# PC_CONNECTIONS.net
KiCad netlist of a schematic drawn in Altium Designer
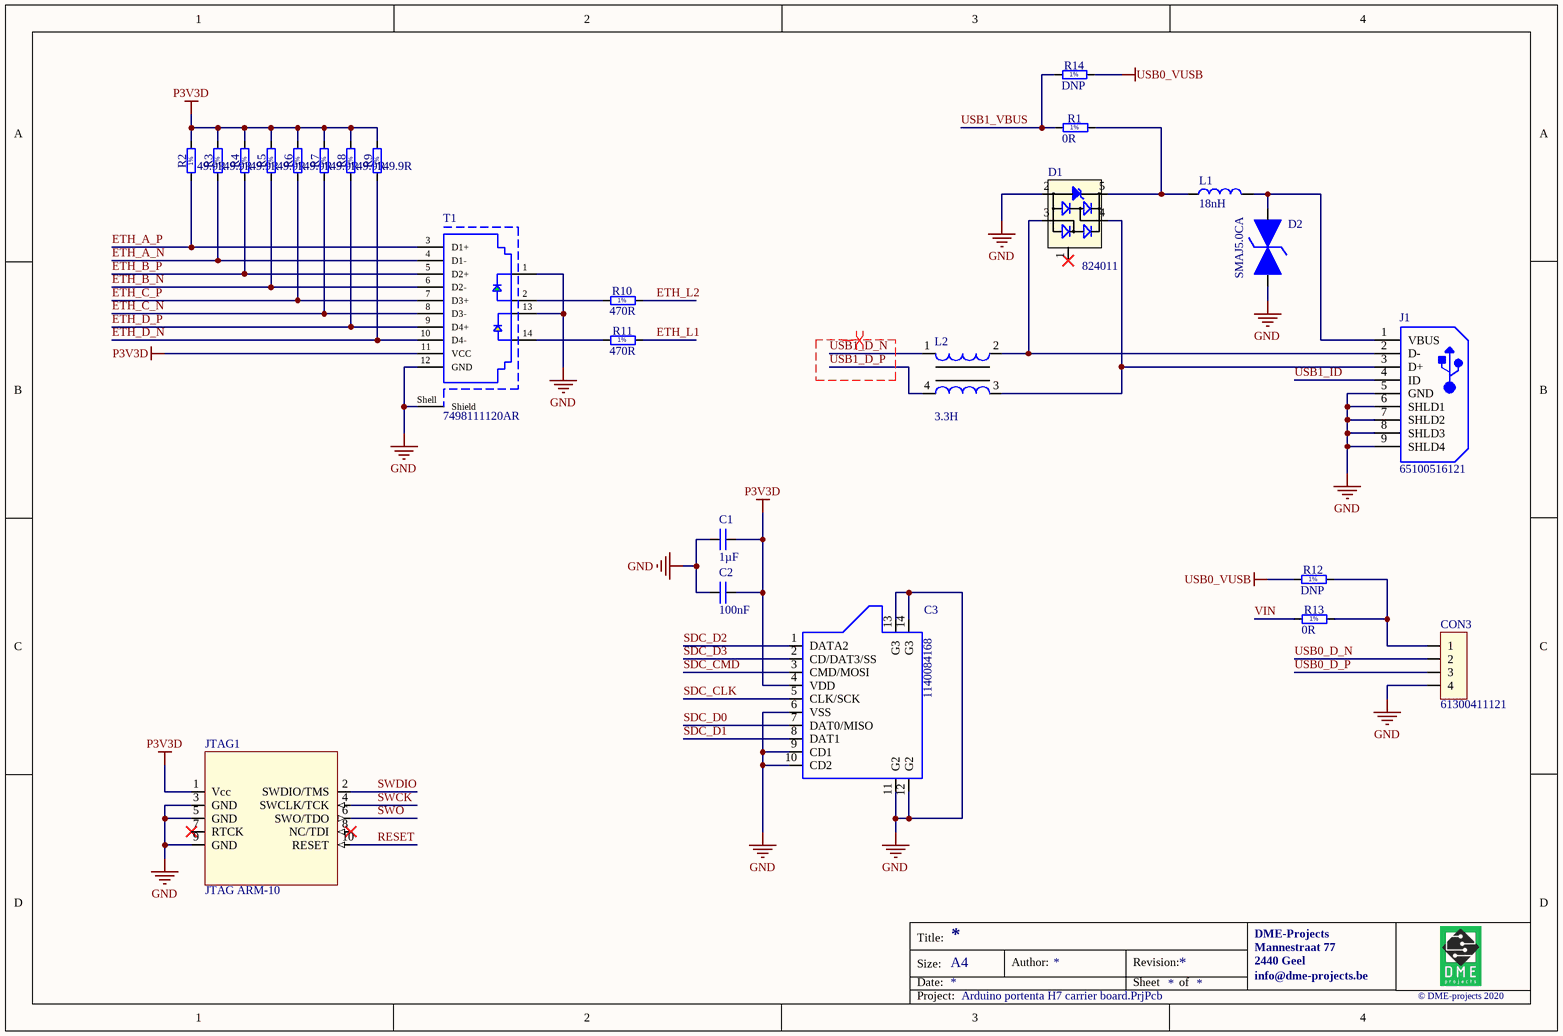
[diagram p0: PC CONNECTIONS.SchDoc]

(export (version "E")
  (design (tool "Eeschema 10.0.6"))
  (components
    (comp (ref "C1")
      (value "1µF")
      (footprint "C0603")
      (description "generic 0603 capacitor")
      (fields (field (name "MFG") "generic") (field (name "TOLERANCE") "0.05"))
      (libsource (lib "MIRION Technologies (CANBERRA Olen) NV") (part "cap"))
    )
    (comp (ref "C2")
      (value "100nF")
      (footprint "C0603")
      (description "generic 0603 capacitor")
      (fields (field (name "TOLERANCE") "0.05") (field (name "MFG") "generic"))
      (libsource (lib "MIRION Technologies (CANBERRA Olen) NV") (part "cap"))
    )
    (comp (ref "C3")
      (value "1140084168")
      (footprint "Amphenol_MicroSD_Connector")
      (description "Micro SD; Conn; IC Socket; ; Right Angle; PCB Mount; MicroSD Ser.")
      (libsource (lib "MIRION Technologies (CANBERRA Olen) NV") (part "1140084168"))
    )
    (comp (ref "CON3")
      (value "61300411121")
      (footprint "61300411121")
      (description "CONN HEADER VERT 4POS 2.54MM")
      (libsource (lib "MIRION Technologies (CANBERRA Olen) NV") (part "CON4"))
    )
    (comp (ref "D1")
      (value "824011")
      (footprint "ATML-5TS1_N")
      (description "Trans Voltage Suppressor Diode, 5V V(RWM), Unidirectional, 1 Element, Silicon")
      (libsource (lib "MIRION Technologies (CANBERRA Olen) NV") (part "WE-TVS-HS-5"))
    )
    (comp (ref "D2")
      (value "SMAJ5.0CA")
      (footprint "FP-SMAJ-MFG")
      (libsource (lib "MIRION Technologies (CANBERRA Olen) NV") (part "be7038aff30a2d1172baa952aa6ae09"))
    )
    (comp (ref "J1")
      (value "65100516121")
      (footprint "WE-65100516121_V")
      (description "CONN RCPT USB2.0 MINI B SMD R/A")
      (libsource (lib "MIRION Technologies (CANBERRA Olen) NV") (part "USB-5-4SHLD"))
    )
    (comp (ref "JTAG1")
      (value "JTAG ARM-10")
      (footprint "62501021621")
      (description "JTAG ARM 10 pin interface connector 2mm pitch")
      (libsource (lib "MIRION Technologies (CANBERRA Olen) NV") (part "10P-JTAG"))
    )
    (comp (ref "L1")
      (value "742792641")
      (footprint "SMD-0603")
      (description "FERRITE BEAD 300 OHM 0603 1LN")
      (fields (field (name "TOLERANCE") "25%") (field (name "INDUCTANCE") "18nH"))
      (libsource (lib "MIRION Technologies (CANBERRA Olen) NV") (part "IND_SINGLE"))
    )
    (comp (ref "L2")
      (value "744232090")
      (footprint "WE-CNSW-1206")
      (description "Data Line Filter, 2 Function(s), 50V, 0.37A")
      (fields (field (name "INDUCTANCE") "3.3H") (field (name "TOLERANCE") "25%"))
      (libsource (lib "MIRION Technologies (CANBERRA Olen) NV") (part "PAS-IND-INDUCTOR-4A"))
    )
    (comp (ref "R1")
      (value "0R")
      (footprint "R0603")
      (description "generic 0603 Thick film resistor")
      (fields (field (name "POWER") "100mW") (field (name "TOLERANCE") "0.01"))
      (libsource (lib "MIRION Technologies (CANBERRA Olen) NV") (part "res_1pct"))
    )
    (comp (ref "R2")
      (value "49.9R")
      (footprint "R0603")
      (description "generic 0603 Thick film resistor")
      (fields (field (name "VOLTAGE") "75V") (field (name "MFG") "generic"))
      (libsource (lib "MIRION Technologies (CANBERRA Olen) NV") (part "res_1pct"))
    )
    (comp (ref "R3")
      (value "49.9R")
      (footprint "R0603")
      (description "generic 0603 Thick film resistor")
      (fields (field (name "VOLTAGE") "75V") (field (name "MFG") "generic"))
      (libsource (lib "MIRION Technologies (CANBERRA Olen) NV") (part "res_1pct"))
    )
    (comp (ref "R4")
      (value "49.9R")
      (footprint "R0603")
      (description "generic 0603 Thick film resistor")
      (fields (field (name "VOLTAGE") "75V") (field (name "MFG") "generic"))
      (libsource (lib "MIRION Technologies (CANBERRA Olen) NV") (part "res_1pct"))
    )
    (comp (ref "R5")
      (value "49.9R")
      (footprint "R0603")
      (description "generic 0603 Thick film resistor")
      (fields (field (name "VOLTAGE") "75V") (field (name "MFG") "generic"))
      (libsource (lib "MIRION Technologies (CANBERRA Olen) NV") (part "res_1pct"))
    )
    (comp (ref "R6")
      (value "49.9R")
      (footprint "R0603")
      (description "generic 0603 Thick film resistor")
      (fields (field (name "VOLTAGE") "75V") (field (name "MFG") "generic"))
      (libsource (lib "MIRION Technologies (CANBERRA Olen) NV") (part "res_1pct"))
    )
    (comp (ref "R7")
      (value "49.9R")
      (footprint "R0603")
      (description "generic 0603 Thick film resistor")
      (fields (field (name "VOLTAGE") "75V") (field (name "MFG") "generic"))
      (libsource (lib "MIRION Technologies (CANBERRA Olen) NV") (part "res_1pct"))
    )
    (comp (ref "R8")
      (value "49.9R")
      (footprint "R0603")
      (description "generic 0603 Thick film resistor")
      (fields (field (name "VOLTAGE") "75V") (field (name "MFG") "generic"))
      (libsource (lib "MIRION Technologies (CANBERRA Olen) NV") (part "res_1pct"))
    )
    (comp (ref "R9")
      (value "49.9R")
      (footprint "R0603")
      (description "generic 0603 Thick film resistor")
      (fields (field (name "VOLTAGE") "75V") (field (name "MFG") "generic"))
      (libsource (lib "MIRION Technologies (CANBERRA Olen) NV") (part "res_1pct"))
    )
    (comp (ref "R10")
      (value "470R")
      (footprint "R0603")
      (description "generic 0603 Thick film resistor")
      (fields (field (name "POWER") "100mW") (field (name "TOLERANCE") "0.01"))
      (libsource (lib "MIRION Technologies (CANBERRA Olen) NV") (part "res_1pct"))
    )
    (comp (ref "R11")
      (value "470R")
      (footprint "R0603")
      (description "generic 0603 Thick film resistor")
      (fields (field (name "POWER") "100mW") (field (name "TOLERANCE") "0.01"))
      (libsource (lib "MIRION Technologies (CANBERRA Olen) NV") (part "res_1pct"))
    )
    (comp (ref "R12")
      (value "DNP")
      (footprint "R0603")
      (description "generic 0603 Thick film resistor")
      (fields (field (name "VOLTAGE") "75V") (field (name "POWER") "100mW"))
      (libsource (lib "MIRION Technologies (CANBERRA Olen) NV") (part "res_1pct"))
    )
    (comp (ref "R13")
      (value "0R")
      (footprint "R0603")
      (description "generic 0603 Thick film resistor")
      (fields (field (name "POWER") "100mW") (field (name "TOLERANCE") "0.01"))
      (libsource (lib "MIRION Technologies (CANBERRA Olen) NV") (part "res_1pct"))
    )
    (comp (ref "R14")
      (value "DNP")
      (footprint "R0603")
      (description "generic 0603 Thick film resistor")
      (fields (field (name "VOLTAGE") "75V") (field (name "POWER") "100mW"))
      (libsource (lib "MIRION Technologies (CANBERRA Olen) NV") (part "res_1pct"))
    )
    (comp (ref "T1")
      (value "7498111120AR")
      (footprint "7498111120AR")
      (description "WE-RJ45 LAN Transformer, SMT, 10/100/1000 Base-T, Port 1x1, Tab Up")
      (fields (field (name "MANUFACTURER") "Wurth Elektronik"))
      (libsource (lib "MIRION Technologies (CANBERRA Olen) NV") (part "7498111120AR"))
    )
  )
  (nets
    (net (code "1") (name "/ETH_A_N") (class "Default")
      (node (ref "R3") (pin "1") (pinfunction "1_1") (pintype "passive"))
      (node (ref "T1") (pin "4") (pinfunction "D1-_4") (pintype "passive"))
    )
    (net (code "2") (name "/ETH_A_P") (class "Default")
      (node (ref "R2") (pin "1") (pinfunction "1_1") (pintype "passive"))
      (node (ref "T1") (pin "3") (pinfunction "D1+_3") (pintype "passive"))
    )
    (net (code "3") (name "/ETH_B_N") (class "Default")
      (node (ref "R5") (pin "1") (pinfunction "1_1") (pintype "passive"))
      (node (ref "T1") (pin "6") (pinfunction "D2-_6") (pintype "passive"))
    )
    (net (code "4") (name "/ETH_B_P") (class "Default")
      (node (ref "R4") (pin "1") (pinfunction "1_1") (pintype "passive"))
      (node (ref "T1") (pin "5") (pinfunction "D2+_5") (pintype "passive"))
    )
    (net (code "5") (name "/ETH_C_N") (class "Default")
      (node (ref "R7") (pin "1") (pinfunction "1_1") (pintype "passive"))
      (node (ref "T1") (pin "8") (pinfunction "D3-_8") (pintype "passive"))
    )
    (net (code "6") (name "/ETH_C_P") (class "Default")
      (node (ref "R6") (pin "1") (pinfunction "1_1") (pintype "passive"))
      (node (ref "T1") (pin "7") (pinfunction "D3+_7") (pintype "passive"))
    )
    (net (code "7") (name "/ETH_D_N") (class "Default")
      (node (ref "R9") (pin "1") (pinfunction "1_1") (pintype "passive"))
      (node (ref "T1") (pin "10") (pinfunction "D4-_10") (pintype "passive"))
    )
    (net (code "8") (name "/ETH_D_P") (class "Default")
      (node (ref "R8") (pin "1") (pinfunction "1_1") (pintype "passive"))
      (node (ref "T1") (pin "9") (pinfunction "D4+_9") (pintype "passive"))
    )
    (net (code "9") (name "/ETH_L1") (class "Default")
      (node (ref "R11") (pin "2") (pinfunction "2_2") (pintype "passive"))
    )
    (net (code "10") (name "/ETH_L2") (class "Default")
      (node (ref "R10") (pin "2") (pinfunction "2_2") (pintype "passive"))
    )
    (net (code "11") (name "/RESET") (class "Default")
      (node (ref "JTAG1") (pin "10") (pinfunction "RESET_10") (pintype "input"))
    )
    (net (code "12") (name "/SDC_CLK") (class "Default")
      (node (ref "C3") (pin "5") (pinfunction "CLK/SCK_5") (pintype "passive"))
    )
    (net (code "13") (name "/SDC_CMD") (class "Default")
      (node (ref "C3") (pin "3") (pinfunction "CMD/MOSI_3") (pintype "passive"))
    )
    (net (code "14") (name "/SDC_D0") (class "Default")
      (node (ref "C3") (pin "7") (pinfunction "DAT0/MISO_7") (pintype "passive"))
    )
    (net (code "15") (name "/SDC_D1") (class "Default")
      (node (ref "C3") (pin "8") (pinfunction "DAT1_8") (pintype "passive"))
    )
    (net (code "16") (name "/SDC_D2") (class "Default")
      (node (ref "C3") (pin "1") (pinfunction "DATA2_1") (pintype "passive"))
    )
    (net (code "17") (name "/SDC_D3") (class "Default")
      (node (ref "C3") (pin "2") (pinfunction "CD/DAT3/SS_2") (pintype "passive"))
    )
    (net (code "18") (name "/SWCK") (class "Default")
      (node (ref "JTAG1") (pin "4") (pinfunction "SWCLK/TCK_4") (pintype "input"))
    )
    (net (code "19") (name "/SWDIO") (class "Default")
      (node (ref "JTAG1") (pin "2") (pinfunction "SWDIO/TMS_2") (pintype "bidirectional"))
    )
    (net (code "20") (name "/SWO") (class "Default")
      (node (ref "JTAG1") (pin "6") (pinfunction "SWO/TDO_6") (pintype "output"))
    )
    (net (code "21") (name "/USB0_D_N") (class "Default")
      (node (ref "CON3") (pin "2") (pinfunction "2_2") (pintype "passive"))
    )
    (net (code "22") (name "/USB0_D_P") (class "Default")
      (node (ref "CON3") (pin "3") (pinfunction "3_3") (pintype "passive"))
    )
    (net (code "23") (name "/USB1_D_N") (class "Default")
      (node (ref "L2") (pin "1") (pinfunction "1_1") (pintype "passive"))
    )
    (net (code "24") (name "/USB1_D_P") (class "Default")
      (node (ref "L2") (pin "4") (pinfunction "4_4") (pintype "passive"))
    )
    (net (code "25") (name "/USB1_ID") (class "Default")
      (node (ref "J1") (pin "4") (pinfunction "ID_4") (pintype "passive"))
    )
    (net (code "26") (name "/USB1_VBUS") (class "Default")
      (node (ref "R1") (pin "1") (pinfunction "1_1") (pintype "passive"))
      (node (ref "R14") (pin "1") (pinfunction "1_1") (pintype "passive"))
    )
    (net (code "27") (name "/VIN") (class "Default")
      (node (ref "R13") (pin "1") (pinfunction "1_1") (pintype "passive"))
    )
    (net (code "28") (name "GND") (class "Default")
      (node (ref "C1") (pin "2") (pinfunction "2_2") (pintype "passive"))
      (node (ref "C2") (pin "1") (pinfunction "1_1") (pintype "passive"))
      (node (ref "C3") (pin "10") (pinfunction "CD2_10") (pintype "passive"))
      (node (ref "C3") (pin "11") (pinfunction "G2_11") (pintype "power_in"))
      (node (ref "C3") (pin "12") (pinfunction "G2_12") (pintype "power_in"))
      (node (ref "C3") (pin "13") (pinfunction "G3_13") (pintype "power_in"))
      (node (ref "C3") (pin "14") (pinfunction "G3_14") (pintype "power_in"))
      (node (ref "C3") (pin "6") (pinfunction "VSS_6") (pintype "power_in"))
      (node (ref "C3") (pin "9") (pinfunction "CD1_9") (pintype "passive"))
      (node (ref "CON3") (pin "4") (pinfunction "4_4") (pintype "passive"))
      (node (ref "D1") (pin "2") (pinfunction "GND_2") (pintype "passive"))
      (node (ref "D2") (pin "1") (pinfunction "1_1") (pintype "passive"))
      (node (ref "J1") (pin "5") (pinfunction "GND_5") (pintype "power_in"))
      (node (ref "J1") (pin "6") (pinfunction "SHLD1_6") (pintype "passive"))
      (node (ref "J1") (pin "7") (pinfunction "SHLD2_7") (pintype "passive"))
      (node (ref "J1") (pin "8") (pinfunction "SHLD3_8") (pintype "passive"))
      (node (ref "J1") (pin "9") (pinfunction "SHLD4_9") (pintype "passive"))
      (node (ref "JTAG1") (pin "3") (pinfunction "GND_3") (pintype "power_in"))
      (node (ref "JTAG1") (pin "5") (pinfunction "GND_5") (pintype "power_in"))
      (node (ref "JTAG1") (pin "9") (pinfunction "GND_9") (pintype "power_in"))
      (node (ref "T1") (pin "1") (pinfunction "1_1") (pintype "passive"))
      (node (ref "T1") (pin "12") (pinfunction "GND_12") (pintype "passive"))
      (node (ref "T1") (pin "13") (pinfunction "13_13") (pintype "passive"))
      (node (ref "T1") (pin "Shell") (pinfunction "Shield_Shell") (pintype "passive"))
    )
    (net (code "29") (name "Net-(CON3-Pad1)") (class "Default")
      (node (ref "CON3") (pin "1") (pinfunction "1_1") (pintype "passive"))
      (node (ref "R12") (pin "2") (pinfunction "2_2") (pintype "passive"))
      (node (ref "R13") (pin "2") (pinfunction "2_2") (pintype "passive"))
    )
    (net (code "30") (name "Net-(D1-I{slash}O1)") (class "Default")
      (node (ref "D1") (pin "3") (pinfunction "I/O1_3") (pintype "passive"))
      (node (ref "J1") (pin "2") (pinfunction "D-_2") (pintype "passive"))
      (node (ref "L2") (pin "2") (pinfunction "2_2") (pintype "passive"))
    )
    (net (code "31") (name "Net-(D1-I{slash}O2)") (class "Default")
      (node (ref "D1") (pin "4") (pinfunction "I/O2_4") (pintype "passive"))
      (node (ref "J1") (pin "3") (pinfunction "D+_3") (pintype "passive"))
      (node (ref "L2") (pin "3") (pinfunction "3_3") (pintype "passive"))
    )
    (net (code "32") (name "Net-(D1-VDD)") (class "Default")
      (node (ref "D1") (pin "5") (pinfunction "VDD_5") (pintype "passive"))
      (node (ref "L1") (pin "1") (pinfunction "1_1") (pintype "passive"))
      (node (ref "R1") (pin "2") (pinfunction "2_2") (pintype "passive"))
    )
    (net (code "33") (name "Net-(J1-VBUS)") (class "Default")
      (node (ref "D2") (pin "2") (pinfunction "2_2") (pintype "passive"))
      (node (ref "J1") (pin "1") (pinfunction "VBUS_1") (pintype "power_in"))
      (node (ref "L1") (pin "2") (pinfunction "2_2") (pintype "passive"))
    )
    (net (code "34") (name "Net-(R10-Pad1)") (class "Default")
      (node (ref "R10") (pin "1") (pinfunction "1_1") (pintype "passive"))
      (node (ref "T1") (pin "2") (pinfunction "2_2") (pintype "passive"))
    )
    (net (code "35") (name "Net-(R11-Pad1)") (class "Default")
      (node (ref "R11") (pin "1") (pinfunction "1_1") (pintype "passive"))
      (node (ref "T1") (pin "14") (pinfunction "14_14") (pintype "passive"))
    )
    (net (code "36") (name "P3V3D") (class "Default")
      (node (ref "C1") (pin "1") (pinfunction "1_1") (pintype "passive"))
      (node (ref "C2") (pin "2") (pinfunction "2_2") (pintype "passive"))
      (node (ref "C3") (pin "4") (pinfunction "VDD_4") (pintype "power_in"))
      (node (ref "JTAG1") (pin "1") (pinfunction "Vcc_1") (pintype "power_in"))
      (node (ref "R2") (pin "2") (pinfunction "2_2") (pintype "passive"))
      (node (ref "R3") (pin "2") (pinfunction "2_2") (pintype "passive"))
      (node (ref "R4") (pin "2") (pinfunction "2_2") (pintype "passive"))
      (node (ref "R5") (pin "2") (pinfunction "2_2") (pintype "passive"))
      (node (ref "R6") (pin "2") (pinfunction "2_2") (pintype "passive"))
      (node (ref "R7") (pin "2") (pinfunction "2_2") (pintype "passive"))
      (node (ref "R8") (pin "2") (pinfunction "2_2") (pintype "passive"))
      (node (ref "R9") (pin "2") (pinfunction "2_2") (pintype "passive"))
      (node (ref "T1") (pin "11") (pinfunction "VCC_11") (pintype "passive"))
    )
    (net (code "37") (name "USB0_VUSB") (class "Default")
      (node (ref "R12") (pin "1") (pinfunction "1_1") (pintype "passive"))
      (node (ref "R14") (pin "2") (pinfunction "2_2") (pintype "passive"))
    )
    (net (code "38") (name "unconnected-(D1-NC-Pad1)") (class "Default")
      (node (ref "D1") (pin "1") (pinfunction "NC_1") (pintype "passive+no_connect"))
    )
    (net (code "39") (name "unconnected-(JTAG1-NC{slash}TDI-Pad8)") (class "Default")
      (node (ref "JTAG1") (pin "8") (pinfunction "NC/TDI_8") (pintype "input+no_connect"))
    )
    (net (code "40") (name "unconnected-(JTAG1-RTCK-Pad7)") (class "Default")
      (node (ref "JTAG1") (pin "7") (pinfunction "RTCK_7") (pintype "passive+no_connect"))
    )
  )
)
